# Esp8266_prot16_v1.net
KiCad netlist of a schematic drawn in EAGLE
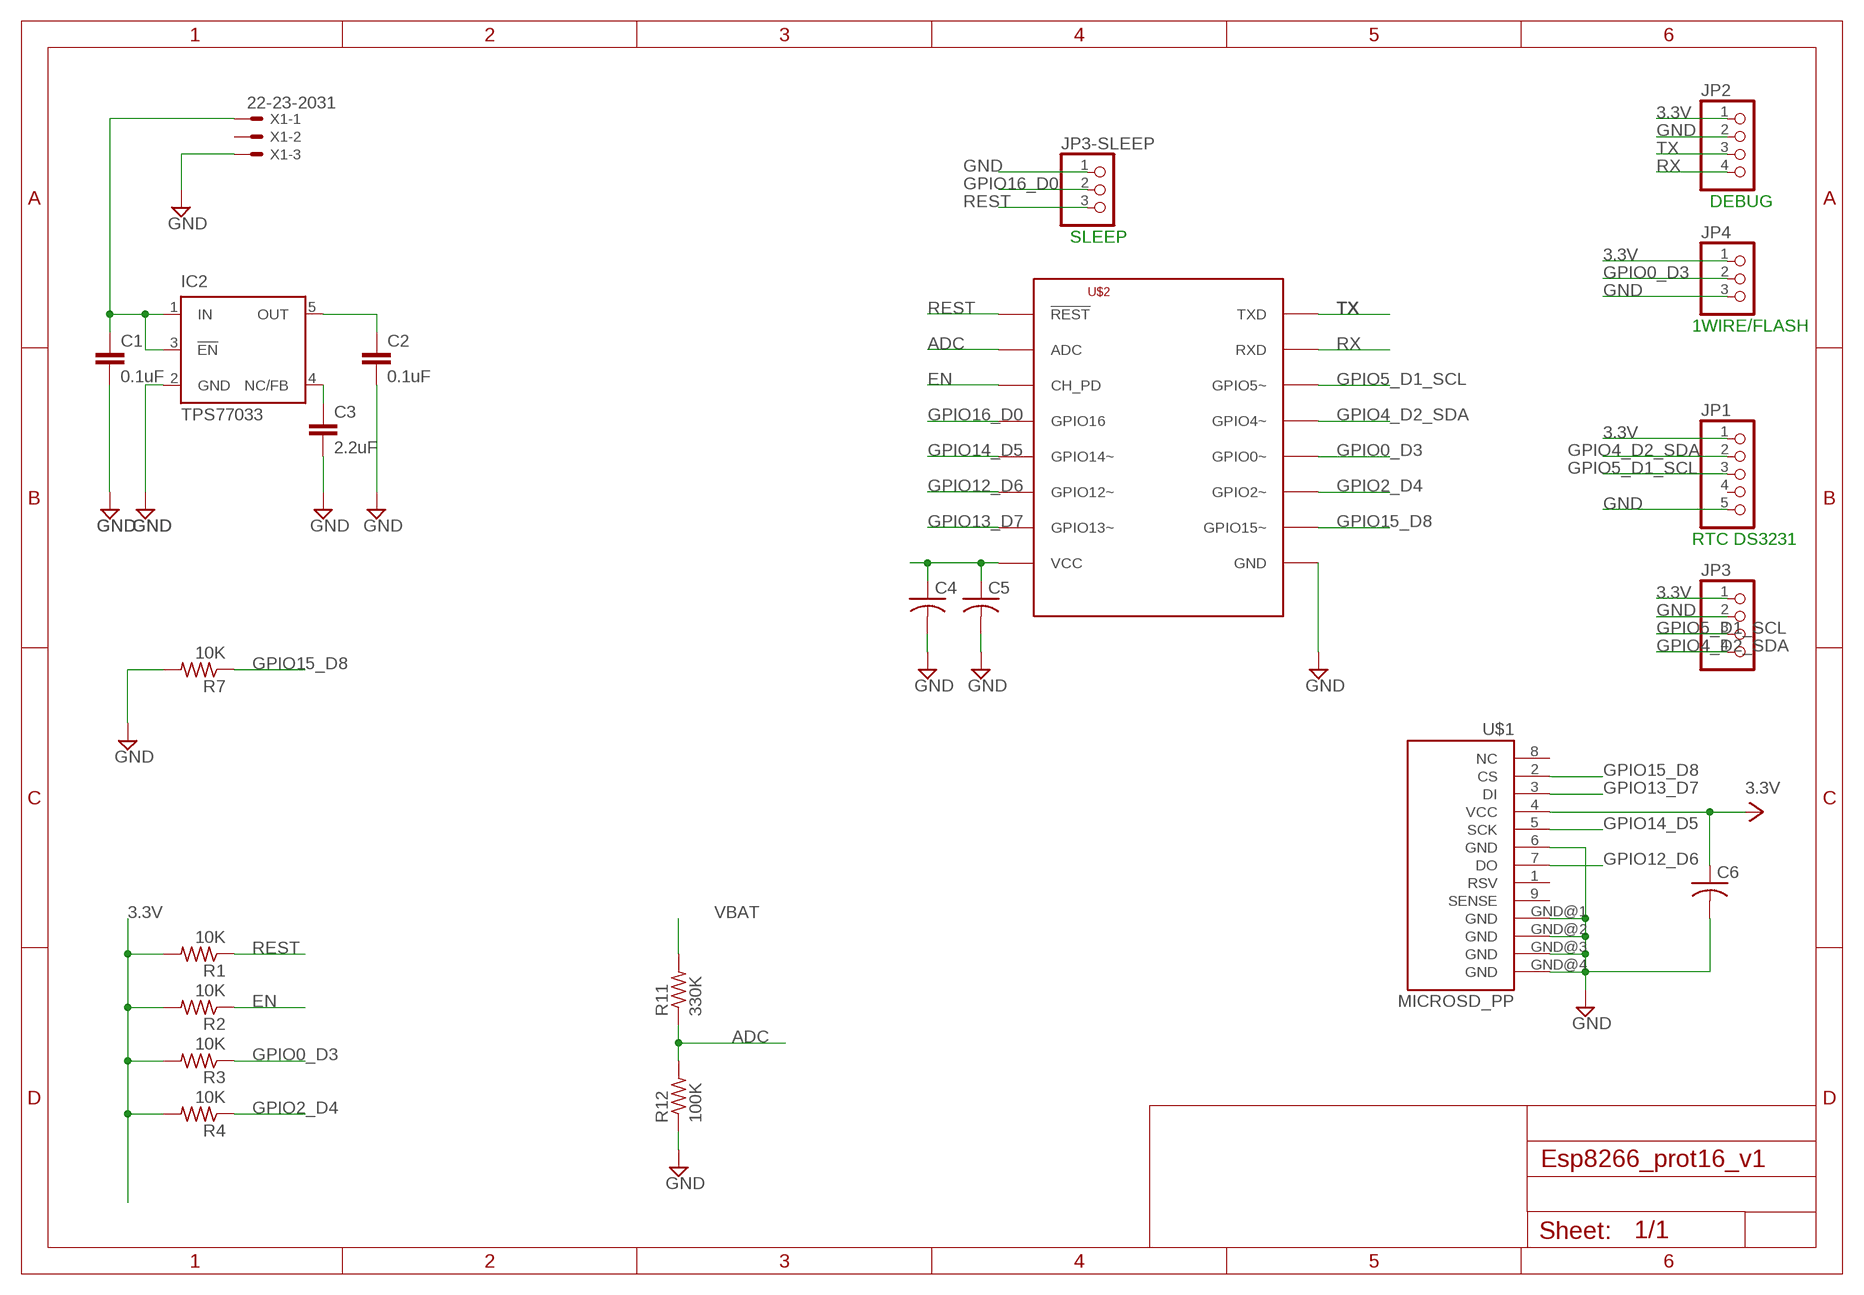
[diagram p0: schematic, sheet 1]

(export (version "E")
  (design (tool "Eeschema 10.0.6"))
  (components
    (comp (ref "C1")
      (value "0.1uF")
      (footprint "eagle-import:C0805")
      (libsource (lib "eagle-import") (part "C-EUC0805"))
    )
    (comp (ref "C2")
      (value "0.1uF")
      (footprint "eagle-import:C0805")
      (libsource (lib "eagle-import") (part "C-EUC0805"))
    )
    (comp (ref "C3")
      (value "2.2uF")
      (footprint "eagle-import:C0805")
      (libsource (lib "eagle-import") (part "C-EUC0805"))
    )
    (comp (ref "C4")
      (value "C-USC1206")
      (footprint "eagle-import:C1206")
      (libsource (lib "eagle-import") (part "C-USC1206"))
    )
    (comp (ref "C5")
      (value "C-USC0805K")
      (footprint "eagle-import:C0805K")
      (libsource (lib "eagle-import") (part "C-USC0805K"))
    )
    (comp (ref "C6")
      (value "C-USC1206")
      (footprint "eagle-import:C1206")
      (libsource (lib "eagle-import") (part "C-USC1206"))
    )
    (comp (ref "IC2")
      (value "TPS77033")
      (footprint "eagle-import:SOT23-DBV")
      (fields
        (field (name "MF") "TEXAS INSTRUMENTS")
        (field (name "MPN") "TPS77033DBVT")
        (field (name "MPN_1") "TPS79301")
      )
      (libsource (lib "eagle-import") (part "TPS77033"))
    )
    (comp (ref "JP1")
      (value "PINHD-1X5")
      (footprint "eagle-import:1X05")
      (libsource (lib "eagle-import") (part "PINHD-1X5"))
    )
    (comp (ref "JP2")
      (value "PINHD-1X4")
      (footprint "eagle-import:1X04")
      (libsource (lib "eagle-import") (part "PINHD-1X4"))
    )
    (comp (ref "JP3")
      (value "PINHD-1X4")
      (footprint "eagle-import:1X04")
      (libsource (lib "eagle-import") (part "PINHD-1X4"))
    )
    (comp (ref "JP3-SLEEP")
      (value "PINHD-1X3")
      (footprint "eagle-import:1X03")
      (libsource (lib "eagle-import") (part "PINHD-1X3"))
    )
    (comp (ref "JP4")
      (value "PINHD-1X3")
      (footprint "eagle-import:1X03")
      (libsource (lib "eagle-import") (part "PINHD-1X3"))
    )
    (comp (ref "R1")
      (value "10K")
      (footprint "eagle-import:M0805")
      (libsource (lib "eagle-import") (part "R-US_M0805"))
    )
    (comp (ref "R2")
      (value "10K")
      (footprint "eagle-import:M0805")
      (libsource (lib "eagle-import") (part "R-US_M0805"))
    )
    (comp (ref "R3")
      (value "10K")
      (footprint "eagle-import:M0805")
      (libsource (lib "eagle-import") (part "R-US_M0805"))
    )
    (comp (ref "R4")
      (value "10K")
      (footprint "eagle-import:R0805")
      (libsource (lib "eagle-import") (part "R-US_R0805"))
    )
    (comp (ref "R7")
      (value "10K")
      (footprint "eagle-import:R0805")
      (libsource (lib "eagle-import") (part "R-US_R0805"))
    )
    (comp (ref "R11")
      (value "330K")
      (footprint "eagle-import:R0805")
      (libsource (lib "eagle-import") (part "R-US_R0805"))
    )
    (comp (ref "R12")
      (value "100K")
      (footprint "eagle-import:R0805")
      (libsource (lib "eagle-import") (part "R-US_R0805"))
    )
    (comp (ref "U$1")
      (value "MICROSD_PP")
      (footprint "eagle-import:MICROSD_PP")
      (libsource (lib "eagle-import") (part "MICROSD_PP"))
    )
    (comp (ref "U$2")
      (value "ESP8266-07")
      (footprint "eagle-import:ESP-07")
      (libsource (lib "eagle-import") (part "ESP8266-07"))
    )
    (comp (ref "X1")
      (value "22-23-2031")
      (footprint "eagle-import:22-23-2031")
      (fields (field (name "MF") "MOLEX"))
      (libsource (lib "eagle-import") (part "22-23-2031"))
    )
  )
  (nets
    (net (code "1") (name "/ADC") (class "Default")
      (node (ref "R11") (pin "1") (pinfunction "1_1") (pintype "passive"))
      (node (ref "R12") (pin "2") (pinfunction "2_2") (pintype "passive"))
      (node (ref "U$2") (pin "ADC") (pinfunction "ADC_ADC") (pintype "input"))
    )
    (net (code "2") (name "/EN") (class "Default")
      (node (ref "R2") (pin "1") (pinfunction "1_1") (pintype "passive"))
      (node (ref "U$2") (pin "CH_PD") (pinfunction "CH_PD_CH_PD") (pintype "input"))
    )
    (net (code "3") (name "/GPIO0_D3") (class "Default")
      (node (ref "JP4") (pin "2") (pinfunction "2_2") (pintype "passive"))
      (node (ref "R3") (pin "1") (pinfunction "1_1") (pintype "passive"))
      (node (ref "U$2") (pin "GPIO0") (pinfunction "GPIO0~{}_GPIO0") (pintype "bidirectional"))
    )
    (net (code "4") (name "/GPIO2_D4") (class "Default")
      (node (ref "R4") (pin "1") (pinfunction "1_1") (pintype "passive"))
      (node (ref "U$2") (pin "GPIO2") (pinfunction "GPIO2~{}_GPIO2") (pintype "bidirectional"))
    )
    (net (code "5") (name "/GPIO4_D2_SDA") (class "Default")
      (node (ref "JP1") (pin "2") (pinfunction "2_2") (pintype "passive"))
      (node (ref "JP3") (pin "4") (pinfunction "4_4") (pintype "passive"))
      (node (ref "U$2") (pin "GPIO5") (pinfunction "GPIO4~{}_GPIO5") (pintype "bidirectional"))
    )
    (net (code "6") (name "/GPIO5_D1_SCL") (class "Default")
      (node (ref "JP1") (pin "3") (pinfunction "3_3") (pintype "passive"))
      (node (ref "JP3") (pin "3") (pinfunction "3_3") (pintype "passive"))
      (node (ref "U$2") (pin "GPIO4") (pinfunction "GPIO5~{}_GPIO4") (pintype "bidirectional"))
    )
    (net (code "7") (name "/GPIO12_D6") (class "Default")
      (node (ref "U$1") (pin "7") (pinfunction "DO_7") (pintype "bidirectional"))
      (node (ref "U$2") (pin "GPIO12") (pinfunction "GPIO12~{}_GPIO12") (pintype "bidirectional"))
    )
    (net (code "8") (name "/GPIO13_D7") (class "Default")
      (node (ref "U$1") (pin "3") (pinfunction "DI_3") (pintype "bidirectional"))
      (node (ref "U$2") (pin "GPIO13") (pinfunction "GPIO13~{}_GPIO13") (pintype "bidirectional"))
    )
    (net (code "9") (name "/GPIO14_D5") (class "Default")
      (node (ref "U$1") (pin "5") (pinfunction "SCK_5") (pintype "bidirectional"))
      (node (ref "U$2") (pin "GPIO14") (pinfunction "GPIO14~{}_GPIO14") (pintype "bidirectional"))
    )
    (net (code "10") (name "/GPIO15_D8") (class "Default")
      (node (ref "R7") (pin "1") (pinfunction "1_1") (pintype "passive"))
      (node (ref "U$1") (pin "2") (pinfunction "CS_2") (pintype "bidirectional"))
      (node (ref "U$2") (pin "GPIO15") (pinfunction "GPIO15~{}_GPIO15") (pintype "bidirectional"))
    )
    (net (code "11") (name "/GPIO16_D0") (class "Default")
      (node (ref "JP3-SLEEP") (pin "2") (pinfunction "2_2") (pintype "passive"))
      (node (ref "U$2") (pin "GPIO16") (pinfunction "GPIO16_GPIO16") (pintype "bidirectional"))
    )
    (net (code "12") (name "/REST") (class "Default")
      (node (ref "JP3-SLEEP") (pin "3") (pinfunction "3_3") (pintype "passive"))
      (node (ref "R1") (pin "1") (pinfunction "1_1") (pintype "passive"))
      (node (ref "U$2") (pin "REST") (pinfunction "~{REST}_REST") (pintype "input"))
    )
    (net (code "13") (name "/RX") (class "Default")
      (node (ref "JP2") (pin "4") (pinfunction "4_4") (pintype "passive"))
      (node (ref "U$2") (pin "RXD") (pinfunction "RXD_RXD") (pintype "input"))
    )
    (net (code "14") (name "/TX") (class "Default")
      (node (ref "JP2") (pin "3") (pinfunction "3_3") (pintype "passive"))
      (node (ref "U$2") (pin "TXD") (pinfunction "TXD_TXD") (pintype "output"))
    )
    (net (code "15") (name "/VBAT") (class "Default")
      (node (ref "C1") (pin "1") (pinfunction "1_1") (pintype "passive"))
      (node (ref "IC2") (pin "1") (pinfunction "IN_1") (pintype "input"))
      (node (ref "IC2") (pin "3") (pinfunction "~{EN}_3") (pintype "input"))
      (node (ref "R11") (pin "2") (pinfunction "2_2") (pintype "passive"))
      (node (ref "X1") (pin "1") (pinfunction "S_1") (pintype "passive"))
    )
    (net (code "16") (name "3.3V") (class "Default")
      (node (ref "C2") (pin "1") (pinfunction "1_1") (pintype "passive"))
      (node (ref "C4") (pin "1") (pinfunction "1_1") (pintype "passive"))
      (node (ref "C5") (pin "1") (pinfunction "1_1") (pintype "passive"))
      (node (ref "C6") (pin "1") (pinfunction "1_1") (pintype "passive"))
      (node (ref "IC2") (pin "5") (pinfunction "OUT_5") (pintype "passive"))
      (node (ref "JP1") (pin "1") (pinfunction "1_1") (pintype "passive"))
      (node (ref "JP2") (pin "1") (pinfunction "1_1") (pintype "passive"))
      (node (ref "JP3") (pin "1") (pinfunction "1_1") (pintype "passive"))
      (node (ref "JP4") (pin "1") (pinfunction "1_1") (pintype "passive"))
      (node (ref "R1") (pin "2") (pinfunction "2_2") (pintype "passive"))
      (node (ref "R2") (pin "2") (pinfunction "2_2") (pintype "passive"))
      (node (ref "R3") (pin "2") (pinfunction "2_2") (pintype "passive"))
      (node (ref "R4") (pin "2") (pinfunction "2_2") (pintype "passive"))
      (node (ref "U$1") (pin "4") (pinfunction "VCC_4") (pintype "bidirectional"))
      (node (ref "U$2") (pin "VCC") (pinfunction "VCC_VCC") (pintype "power_in"))
    )
    (net (code "17") (name "GND") (class "Default")
      (node (ref "C1") (pin "2") (pinfunction "2_2") (pintype "passive"))
      (node (ref "C2") (pin "2") (pinfunction "2_2") (pintype "passive"))
      (node (ref "C3") (pin "2") (pinfunction "2_2") (pintype "passive"))
      (node (ref "C4") (pin "2") (pinfunction "2_2") (pintype "passive"))
      (node (ref "C5") (pin "2") (pinfunction "2_2") (pintype "passive"))
      (node (ref "C6") (pin "2") (pinfunction "2_2") (pintype "passive"))
      (node (ref "IC2") (pin "2") (pinfunction "GND_2") (pintype "power_in"))
      (node (ref "JP1") (pin "5") (pinfunction "5_5") (pintype "passive"))
      (node (ref "JP2") (pin "2") (pinfunction "2_2") (pintype "passive"))
      (node (ref "JP3") (pin "2") (pinfunction "2_2") (pintype "passive"))
      (node (ref "JP3-SLEEP") (pin "1") (pinfunction "1_1") (pintype "passive"))
      (node (ref "JP4") (pin "3") (pinfunction "3_3") (pintype "passive"))
      (node (ref "R12") (pin "1") (pinfunction "1_1") (pintype "passive"))
      (node (ref "R7") (pin "2") (pinfunction "2_2") (pintype "passive"))
      (node (ref "U$1") (pin "6") (pinfunction "GND_6") (pintype "bidirectional"))
      (node (ref "U$1") (pin "GND@1") (pinfunction "GND_GND@1") (pintype "bidirectional"))
      (node (ref "U$1") (pin "GND@2") (pinfunction "GND_GND@2") (pintype "bidirectional"))
      (node (ref "U$1") (pin "GND@3") (pinfunction "GND_GND@3") (pintype "bidirectional"))
      (node (ref "U$1") (pin "GND@4") (pinfunction "GND_GND@4") (pintype "bidirectional"))
      (node (ref "U$2") (pin "GND") (pinfunction "GND_GND") (pintype "power_in"))
      (node (ref "X1") (pin "3") (pinfunction "S_3") (pintype "passive"))
    )
    (net (code "18") (name "Net-(IC2-NC{slash}FB)") (class "Default")
      (node (ref "C3") (pin "1") (pinfunction "1_1") (pintype "passive"))
      (node (ref "IC2") (pin "4") (pinfunction "NC/FB_4") (pintype "passive"))
    )
    (net (code "19") (name "unconnected-(JP1-Pad4)") (class "Default")
      (node (ref "JP1") (pin "4") (pinfunction "4_4") (pintype "passive"))
    )
    (net (code "20") (name "unconnected-(U$1-NC-Pad8)") (class "Default")
      (node (ref "U$1") (pin "8") (pinfunction "NC_8") (pintype "bidirectional"))
    )
    (net (code "21") (name "unconnected-(U$1-RSV-Pad1)") (class "Default")
      (node (ref "U$1") (pin "1") (pinfunction "RSV_1") (pintype "bidirectional"))
    )
    (net (code "22") (name "unconnected-(U$1-SENSE-Pad9)") (class "Default")
      (node (ref "U$1") (pin "9") (pinfunction "SENSE_9") (pintype "bidirectional"))
    )
    (net (code "23") (name "unconnected-(X1B-S-Pad2)") (class "Default")
      (node (ref "X1") (pin "2") (pinfunction "S_2") (pintype "passive"))
    )
  )
)
